# 1_P1_schdoc.net
KiCad netlist of a schematic drawn in Altium Designer
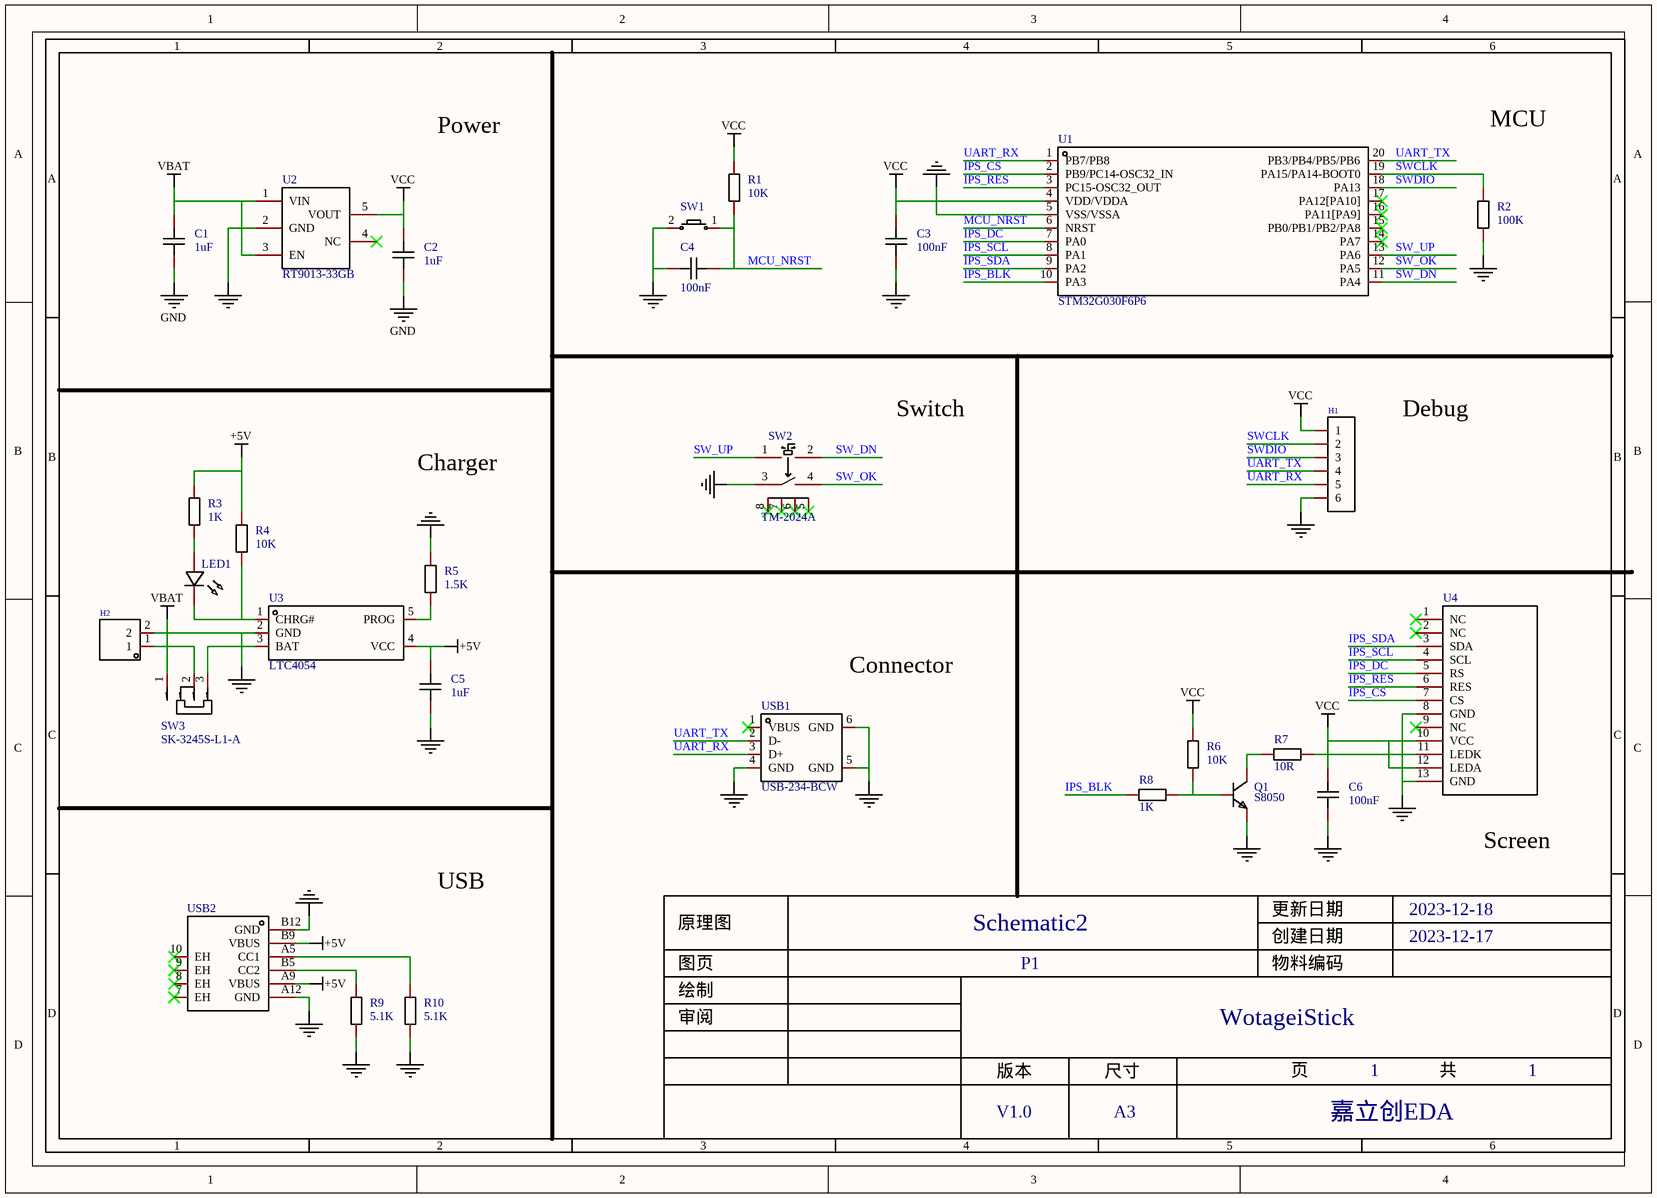
[diagram p0: 1_P1.schdoc.schdoc]

(export (version "E")
  (design (tool "Eeschema 10.0.6"))
  (components
    (comp (ref "C1")
      (value "1uF")
      (fields (field (name "NAME") "1uF"))
      (libsource (lib "altium-import") (part "root_1_CAP_0603_"))
    )
    (comp (ref "C2")
      (value "1uF")
      (fields (field (name "NAME") "1uF"))
      (libsource (lib "altium-import") (part "root_1_CAP_0603_"))
    )
    (comp (ref "C3")
      (value "100nF")
      (fields (field (name "NAME") "100nF"))
      (libsource (lib "altium-import") (part "root_1_CAP_0603_"))
    )
    (comp (ref "C4")
      (value "100nF")
      (fields (field (name "NAME") "100nF"))
      (libsource (lib "altium-import") (part "root_2_mirrored_CAP_0603_"))
    )
    (comp (ref "C5")
      (value "1uF")
      (fields (field (name "NAME") "1uF"))
      (libsource (lib "altium-import") (part "root_1_CAP_0603_"))
    )
    (comp (ref "C6")
      (value "100nF")
      (fields (field (name "NAME") "100nF"))
      (libsource (lib "altium-import") (part "root_1_CAP_0603_"))
    )
    (comp (ref "H1")
      (value "HDR-M_2.54_1x6P")
      (fields (field (name "MANUFACTURER") "BOOMELE(博穆精密)") (field (name "MANUFACTURER PART") "2.54-1x6P直针"))
      (libsource (lib "altium-import") (part "root_0_HDR-M_2.54_1x6P_"))
    )
    (comp (ref "H2")
      (value "HDR-M_2.54_1x2P")
      (fields (field (name "MANUFACTURER") "Ckmtw(灿科盟)") (field (name "MANUFACTURER PART") "B-2100S02P-A110"))
      (libsource (lib "altium-import") (part "root_2_HDR-M_2.54_1x2P_"))
    )
    (comp (ref "LED1") (value "LED_0603-R") (libsource (lib "altium-import") (part "root_3_LED_0603-R_")))
    (comp (ref "Q1")
      (value "S8050")
      (description "晶体管类型:NPN;集电极电流(Ic):500mA;集射极击穿电压(Vceo):25V;功率(Pd):300mW;")
      (fields (field (name "NAME") "S8050") (field (name "MANUFACTURER") "YONGYUTAI(永裕泰)"))
      (libsource (lib "altium-import") (part "root_0_S8050_C2891804_"))
    )
    (comp (ref "R1")
      (value "10K")
      (fields (field (name "NAME") "10K"))
      (libsource (lib "altium-import") (part "root_3_mirrored_Res_0603_"))
    )
    (comp (ref "R2")
      (value "100K")
      (fields (field (name "NAME") "100K"))
      (libsource (lib "altium-import") (part "root_3_Res_0603_"))
    )
    (comp (ref "R3")
      (value "1K")
      (fields (field (name "NAME") "1K"))
      (libsource (lib "altium-import") (part "root_3_Res_0603_"))
    )
    (comp (ref "R4")
      (value "10K")
      (fields (field (name "NAME") "10K"))
      (libsource (lib "altium-import") (part "root_3_Res_0603_"))
    )
    (comp (ref "R5")
      (value "1.5K")
      (fields (field (name "NAME") "1.5K"))
      (libsource (lib "altium-import") (part "root_3_Res_0603_"))
    )
    (comp (ref "R6")
      (value "10K")
      (fields (field (name "NAME") "10K"))
      (libsource (lib "altium-import") (part "root_1_Res_0603_"))
    )
    (comp (ref "R7")
      (value "10R")
      (fields (field (name "NAME") "10R"))
      (libsource (lib "altium-import") (part "root_0_Res_0603_"))
    )
    (comp (ref "R8")
      (value "1K")
      (fields (field (name "NAME") "1K"))
      (libsource (lib "altium-import") (part "root_0_Res_0603_"))
    )
    (comp (ref "R9")
      (value "5.1K")
      (fields (field (name "NAME") "5.1K"))
      (libsource (lib "altium-import") (part "root_1_Res_0603_"))
    )
    (comp (ref "R10")
      (value "5.1K")
      (fields (field (name "NAME") "5.1K"))
      (libsource (lib "altium-import") (part "root_3_Res_0603_"))
    )
    (comp (ref "SW1")
      (value "Key_SMD_3x4x2")
      (libsource (lib "altium-import") (part "root_0_mirrored_Key_SMD_3x4x2_"))
    )
    (comp (ref "SW2")
      (value "TM-2024A")
      (fields (field (name "NAME") "TM-2024A") (field (name "MANUFACTURER") "XKB Connectivity(中国星坤)"))
      (libsource (lib "altium-import") (part "root_0_TM-2024A_"))
    )
    (comp (ref "SW3")
      (value "SK-3245S-L1-A")
      (description "电路结构:双刀双掷;安装方式:卧贴;开关颜色:黑色;额定电流(DC):50mA;额定电压(DC):12V;额定电流(AC):50mA;额定电压(AC):12V;机械寿命:1万次;")
      (fields (field (name "NAME") "SK-3245S-L1-A") (field (name "MANUFACTURER") "XKB Connectivity(中国星坤)"))
      (libsource (lib "altium-import") (part "root_0_SK-3245S-L1-A_"))
    )
    (comp (ref "U1")
      (value "STM32G030F6P6")
      (fields (field (name "NAME") "STM32G030F6P6") (field (name "MANUFACTURER") "ST(意法半导体)"))
      (libsource (lib "altium-import") (part "root_0_STM32G030F6P6_"))
    )
    (comp (ref "U2")
      (value "RT9013-33GB")
      (description "输出类型:固定;输出极性:正;最大输入电压:5.5V;输出电压:3.3V;输出电流:500mA;电源纹波抑制比(PSRR):50dB@(10kHz);")
      (fields (field (name "NAME") "RT9013-33GB") (field (name "MANUFACTURER") "RICHTEK(立锜)"))
      (libsource (lib "altium-import") (part "root_0_RT9013-33GB_"))
    )
    (comp (ref "U3")
      (value "LTC4054")
      (description "具有热调节功能的独立线性锂离子电池充电器")
      (fields (field (name "NAME") "LTC4054") (field (name "MANUFACTURER") "ADI(亚德诺)/LINEAR(凌特)"))
      (libsource (lib "altium-import") (part "root_0_LTC4054ES5-4.2#PBF_"))
    )
    (comp (ref "U4")
      (value "TFT显示模块 0.96寸TFT 13PIN ST7735S")
      (libsource (lib "altium-import") (part "root_0_TFT显示模块 0.96寸TFT 13PIN ST7735S_"))
    )
    (comp (ref "USB1")
      (value "USB-234-BCW")
      (fields (field (name "NAME") "USB-234-BCW") (field (name "MANUFACTURER") "XUNPU(讯普)"))
      (libsource (lib "altium-import") (part "root_0_USB-234-BCW_"))
    )
    (comp (ref "USB2")
      (value "USB_ Type-C-6P")
      (libsource (lib "altium-import") (part "root_0_USB_ Type-C-6P_"))
    )
  )
  (nets
    (net (code "1") (name "+5V") (class "Default")
      (node (ref "C5") (pin "2") (pinfunction "2_2") (pintype "passive"))
      (node (ref "R3") (pin "1") (pinfunction "1_1") (pintype "passive"))
      (node (ref "R4") (pin "1") (pinfunction "1_1") (pintype "passive"))
      (node (ref "U3") (pin "4") (pinfunction "VCC_4") (pintype "passive"))
      (node (ref "USB2") (pin "A9") (pinfunction "VBUS_A9") (pintype "passive"))
      (node (ref "USB2") (pin "B9") (pinfunction "VBUS_B9") (pintype "passive"))
    )
    (net (code "2") (name "/IPS_BLK") (class "Default")
      (node (ref "R8") (pin "1") (pinfunction "1_1") (pintype "passive"))
      (node (ref "U1") (pin "10") (pinfunction "PA3_10") (pintype "passive"))
    )
    (net (code "3") (name "/IPS_CS") (class "Default")
      (node (ref "U1") (pin "2") (pinfunction "PB9/PC14-OSC32_IN_2") (pintype "passive"))
      (node (ref "U4") (pin "7") (pinfunction "CS_7") (pintype "passive"))
    )
    (net (code "4") (name "/IPS_DC") (class "Default")
      (node (ref "U1") (pin "7") (pinfunction "PA0_7") (pintype "passive"))
      (node (ref "U4") (pin "5") (pinfunction "RS_5") (pintype "passive"))
    )
    (net (code "5") (name "/IPS_RES") (class "Default")
      (node (ref "U1") (pin "3") (pinfunction "PC15-OSC32_OUT_3") (pintype "passive"))
      (node (ref "U4") (pin "6") (pinfunction "RES_6") (pintype "passive"))
    )
    (net (code "6") (name "/IPS_SCL") (class "Default")
      (node (ref "U1") (pin "8") (pinfunction "PA1_8") (pintype "passive"))
      (node (ref "U4") (pin "4") (pinfunction "SCL_4") (pintype "passive"))
    )
    (net (code "7") (name "/IPS_SDA") (class "Default")
      (node (ref "U1") (pin "9") (pinfunction "PA2_9") (pintype "passive"))
      (node (ref "U4") (pin "3") (pinfunction "SDA_3") (pintype "passive"))
    )
    (net (code "8") (name "/MCU_NRST") (class "Default")
      (node (ref "C4") (pin "2") (pinfunction "2_2") (pintype "passive"))
      (node (ref "R1") (pin "2") (pinfunction "2_2") (pintype "passive"))
      (node (ref "SW1") (pin "1") (pinfunction "1_1") (pintype "passive"))
      (node (ref "U1") (pin "6") (pinfunction "NRST_6") (pintype "passive"))
    )
    (net (code "9") (name "/SWCLK") (class "Default")
      (node (ref "H1") (pin "2") (pinfunction "2_2") (pintype "passive"))
      (node (ref "R2") (pin "1") (pinfunction "1_1") (pintype "passive"))
      (node (ref "U1") (pin "19") (pinfunction "PA15/PA14-BOOT0_19") (pintype "passive"))
    )
    (net (code "10") (name "/SWDIO") (class "Default")
      (node (ref "H1") (pin "3") (pinfunction "3_3") (pintype "passive"))
      (node (ref "U1") (pin "18") (pinfunction "PA13_18") (pintype "passive"))
    )
    (net (code "11") (name "/SW_DN") (class "Default")
      (node (ref "SW2") (pin "2") (pinfunction "2_2") (pintype "passive"))
      (node (ref "U1") (pin "11") (pinfunction "PA4_11") (pintype "passive"))
    )
    (net (code "12") (name "/SW_OK") (class "Default")
      (node (ref "SW2") (pin "4") (pinfunction "4_4") (pintype "passive"))
      (node (ref "U1") (pin "12") (pinfunction "PA5_12") (pintype "passive"))
    )
    (net (code "13") (name "/SW_UP") (class "Default")
      (node (ref "SW2") (pin "1") (pinfunction "1_1") (pintype "passive"))
      (node (ref "U1") (pin "13") (pinfunction "PA6_13") (pintype "passive"))
    )
    (net (code "14") (name "/UART_RX") (class "Default")
      (node (ref "H1") (pin "5") (pinfunction "5_5") (pintype "passive"))
      (node (ref "U1") (pin "1") (pinfunction "PB7/PB8_1") (pintype "passive"))
      (node (ref "USB1") (pin "3") (pinfunction "D+_3") (pintype "passive"))
    )
    (net (code "15") (name "/UART_TX") (class "Default")
      (node (ref "H1") (pin "4") (pinfunction "4_4") (pintype "passive"))
      (node (ref "U1") (pin "20") (pinfunction "PB3/PB4/PB5/PB6_20") (pintype "passive"))
      (node (ref "USB1") (pin "2") (pinfunction "D-_2") (pintype "passive"))
    )
    (net (code "16") (name "<NO NET>") (class "Default")
      (node (ref "C3") (pin "1") (pinfunction "1_1") (pintype "passive"))
      (node (ref "C4") (pin "1") (pinfunction "1_1") (pintype "passive"))
      (node (ref "C5") (pin "1") (pinfunction "1_1") (pintype "passive"))
      (node (ref "C6") (pin "1") (pinfunction "1_1") (pintype "passive"))
      (node (ref "H1") (pin "6") (pinfunction "6_6") (pintype "passive"))
      (node (ref "H2") (pin "2") (pinfunction "2_2") (pintype "passive"))
      (node (ref "Q1") (pin "2") (pinfunction "E_2") (pintype "passive"))
      (node (ref "R10") (pin "2") (pinfunction "2_2") (pintype "passive"))
      (node (ref "R2") (pin "2") (pinfunction "2_2") (pintype "passive"))
      (node (ref "R5") (pin "1") (pinfunction "1_1") (pintype "passive"))
      (node (ref "R9") (pin "1") (pinfunction "1_1") (pintype "passive"))
      (node (ref "SW1") (pin "2") (pinfunction "2_2") (pintype "passive"))
      (node (ref "SW2") (pin "3") (pinfunction "3_3") (pintype "passive"))
      (node (ref "U1") (pin "5") (pinfunction "VSS/VSSA_5") (pintype "passive"))
      (node (ref "U2") (pin "2") (pinfunction "GND_2") (pintype "passive"))
      (node (ref "U3") (pin "2") (pinfunction "GND_2") (pintype "passive"))
      (node (ref "U4") (pin "13") (pinfunction "GND_13") (pintype "passive"))
      (node (ref "U4") (pin "8") (pinfunction "GND_8") (pintype "passive"))
      (node (ref "USB1") (pin "4") (pinfunction "GND_4") (pintype "passive"))
      (node (ref "USB1") (pin "5") (pinfunction "GND_5") (pintype "passive"))
      (node (ref "USB1") (pin "6") (pinfunction "GND_6") (pintype "passive"))
      (node (ref "USB2") (pin "A12") (pinfunction "GND_A12") (pintype "passive"))
      (node (ref "USB2") (pin "B12") (pinfunction "GND_B12") (pintype "passive"))
    )
    (net (code "17") (name "GND") (class "Default")
      (node (ref "C1") (pin "1") (pinfunction "1_1") (pintype "passive"))
      (node (ref "C2") (pin "1") (pinfunction "1_1") (pintype "passive"))
    )
    (net (code "18") (name "Net-(H2-Pad1)") (class "Default")
      (node (ref "H2") (pin "1") (pinfunction "1_1") (pintype "passive"))
      (node (ref "SW3") (pin "2") (pinfunction "2_2") (pintype "passive"))
    )
    (net (code "19") (name "Net-(LED1-A)") (class "Default")
      (node (ref "LED1") (pin "2") (pinfunction "A_2") (pintype "passive"))
      (node (ref "R3") (pin "2") (pinfunction "2_2") (pintype "passive"))
    )
    (net (code "20") (name "Net-(LED1-C)") (class "Default")
      (node (ref "LED1") (pin "1") (pinfunction "C_1") (pintype "passive"))
      (node (ref "R4") (pin "2") (pinfunction "2_2") (pintype "passive"))
      (node (ref "U3") (pin "1") (pinfunction "CHRG#_1") (pintype "passive"))
    )
    (net (code "21") (name "Net-(Q1-B)") (class "Default")
      (node (ref "Q1") (pin "1") (pinfunction "B_1") (pintype "passive"))
      (node (ref "R6") (pin "1") (pinfunction "1_1") (pintype "passive"))
      (node (ref "R8") (pin "2") (pinfunction "2_2") (pintype "passive"))
    )
    (net (code "22") (name "Net-(Q1-C)") (class "Default")
      (node (ref "Q1") (pin "3") (pinfunction "C_3") (pintype "passive"))
      (node (ref "R7") (pin "1") (pinfunction "1_1") (pintype "passive"))
    )
    (net (code "23") (name "Net-(U3-BAT)") (class "Default")
      (node (ref "SW3") (pin "3") (pinfunction "3_3") (pintype "passive"))
      (node (ref "U3") (pin "3") (pinfunction "BAT_3") (pintype "passive"))
    )
    (net (code "24") (name "Net-(U3-PROG)") (class "Default")
      (node (ref "R5") (pin "2") (pinfunction "2_2") (pintype "passive"))
      (node (ref "U3") (pin "5") (pinfunction "PROG_5") (pintype "passive"))
    )
    (net (code "25") (name "Net-(U4-LEDK)") (class "Default")
      (node (ref "R7") (pin "2") (pinfunction "2_2") (pintype "passive"))
      (node (ref "U4") (pin "11") (pinfunction "LEDK_11") (pintype "passive"))
    )
    (net (code "26") (name "Net-(USB2-CC1)") (class "Default")
      (node (ref "R10") (pin "1") (pinfunction "1_1") (pintype "passive"))
      (node (ref "USB2") (pin "A5") (pinfunction "CC1_A5") (pintype "passive"))
    )
    (net (code "27") (name "Net-(USB2-CC2)") (class "Default")
      (node (ref "R9") (pin "2") (pinfunction "2_2") (pintype "passive"))
      (node (ref "USB2") (pin "B5") (pinfunction "CC2_B5") (pintype "passive"))
    )
    (net (code "28") (name "VBAT") (class "Default")
      (node (ref "C1") (pin "2") (pinfunction "2_2") (pintype "passive"))
      (node (ref "SW3") (pin "1") (pinfunction "1_1") (pintype "passive"))
      (node (ref "U2") (pin "1") (pinfunction "VIN_1") (pintype "passive"))
      (node (ref "U2") (pin "3") (pinfunction "EN_3") (pintype "passive"))
    )
    (net (code "29") (name "VCC") (class "Default")
      (node (ref "C2") (pin "2") (pinfunction "2_2") (pintype "passive"))
      (node (ref "C3") (pin "2") (pinfunction "2_2") (pintype "passive"))
      (node (ref "C6") (pin "2") (pinfunction "2_2") (pintype "passive"))
      (node (ref "H1") (pin "1") (pinfunction "1_1") (pintype "passive"))
      (node (ref "R1") (pin "1") (pinfunction "1_1") (pintype "passive"))
      (node (ref "R6") (pin "2") (pinfunction "2_2") (pintype "passive"))
      (node (ref "U1") (pin "4") (pinfunction "VDD/VDDA_4") (pintype "passive"))
      (node (ref "U2") (pin "5") (pinfunction "VOUT_5") (pintype "passive"))
      (node (ref "U4") (pin "10") (pinfunction "VCC_10") (pintype "passive"))
      (node (ref "U4") (pin "12") (pinfunction "LEDA_12") (pintype "passive"))
    )
    (net (code "30") (name "unconnected-(SW2-Pad5)") (class "Default")
      (node (ref "SW2") (pin "5") (pinfunction "5_5") (pintype "passive+no_connect"))
    )
    (net (code "31") (name "unconnected-(SW2-Pad6)") (class "Default")
      (node (ref "SW2") (pin "6") (pinfunction "6_6") (pintype "passive+no_connect"))
    )
    (net (code "32") (name "unconnected-(SW2-Pad7)") (class "Default")
      (node (ref "SW2") (pin "7") (pinfunction "7_7") (pintype "passive+no_connect"))
    )
    (net (code "33") (name "unconnected-(SW2-Pad8)") (class "Default")
      (node (ref "SW2") (pin "8") (pinfunction "8_8") (pintype "passive+no_connect"))
    )
    (net (code "34") (name "unconnected-(U1-PA7-Pad14)") (class "Default")
      (node (ref "U1") (pin "14") (pinfunction "PA7_14") (pintype "passive+no_connect"))
    )
    (net (code "35") (name "unconnected-(U1-PA11[PA9]-Pad16)") (class "Default")
      (node (ref "U1") (pin "16") (pinfunction "PA11[PA9]_16") (pintype "passive+no_connect"))
    )
    (net (code "36") (name "unconnected-(U1-PA12[PA10]-Pad17)") (class "Default")
      (node (ref "U1") (pin "17") (pinfunction "PA12[PA10]_17") (pintype "passive+no_connect"))
    )
    (net (code "37") (name "unconnected-(U1-PB0{slash}PB1{slash}PB2{slash}PA8-Pad15)") (class "Default")
      (node (ref "U1") (pin "15") (pinfunction "PB0/PB1/PB2/PA8_15") (pintype "passive+no_connect"))
    )
    (net (code "38") (name "unconnected-(U2-NC-Pad4)") (class "Default")
      (node (ref "U2") (pin "4") (pinfunction "NC_4") (pintype "passive+no_connect"))
    )
    (net (code "39") (name "unconnected-(U4-NC-Pad1)") (class "Default")
      (node (ref "U4") (pin "1") (pinfunction "NC_1") (pintype "passive+no_connect"))
    )
    (net (code "40") (name "unconnected-(U4-NC-Pad2)") (class "Default")
      (node (ref "U4") (pin "2") (pinfunction "NC_2") (pintype "passive+no_connect"))
    )
    (net (code "41") (name "unconnected-(U4-NC-Pad9)") (class "Default")
      (node (ref "U4") (pin "9") (pinfunction "NC_9") (pintype "passive+no_connect"))
    )
    (net (code "42") (name "unconnected-(USB1-VBUS-Pad1)") (class "Default")
      (node (ref "USB1") (pin "1") (pinfunction "VBUS_1") (pintype "passive+no_connect"))
    )
    (net (code "43") (name "unconnected-(USB2-EH-Pad7)") (class "Default")
      (node (ref "USB2") (pin "7") (pinfunction "EH_7") (pintype "passive"))
    )
    (net (code "44") (name "unconnected-(USB2-EH-Pad8)") (class "Default")
      (node (ref "USB2") (pin "8") (pinfunction "EH_8") (pintype "passive"))
    )
    (net (code "45") (name "unconnected-(USB2-EH-Pad9)") (class "Default")
      (node (ref "USB2") (pin "9") (pinfunction "EH_9") (pintype "passive"))
    )
    (net (code "46") (name "unconnected-(USB2-EH-Pad10)") (class "Default")
      (node (ref "USB2") (pin "10") (pinfunction "EH_10") (pintype "passive"))
    )
  )
)
